# LTC2983_Group.net
KiCad netlist of a schematic drawn in Altium Designer
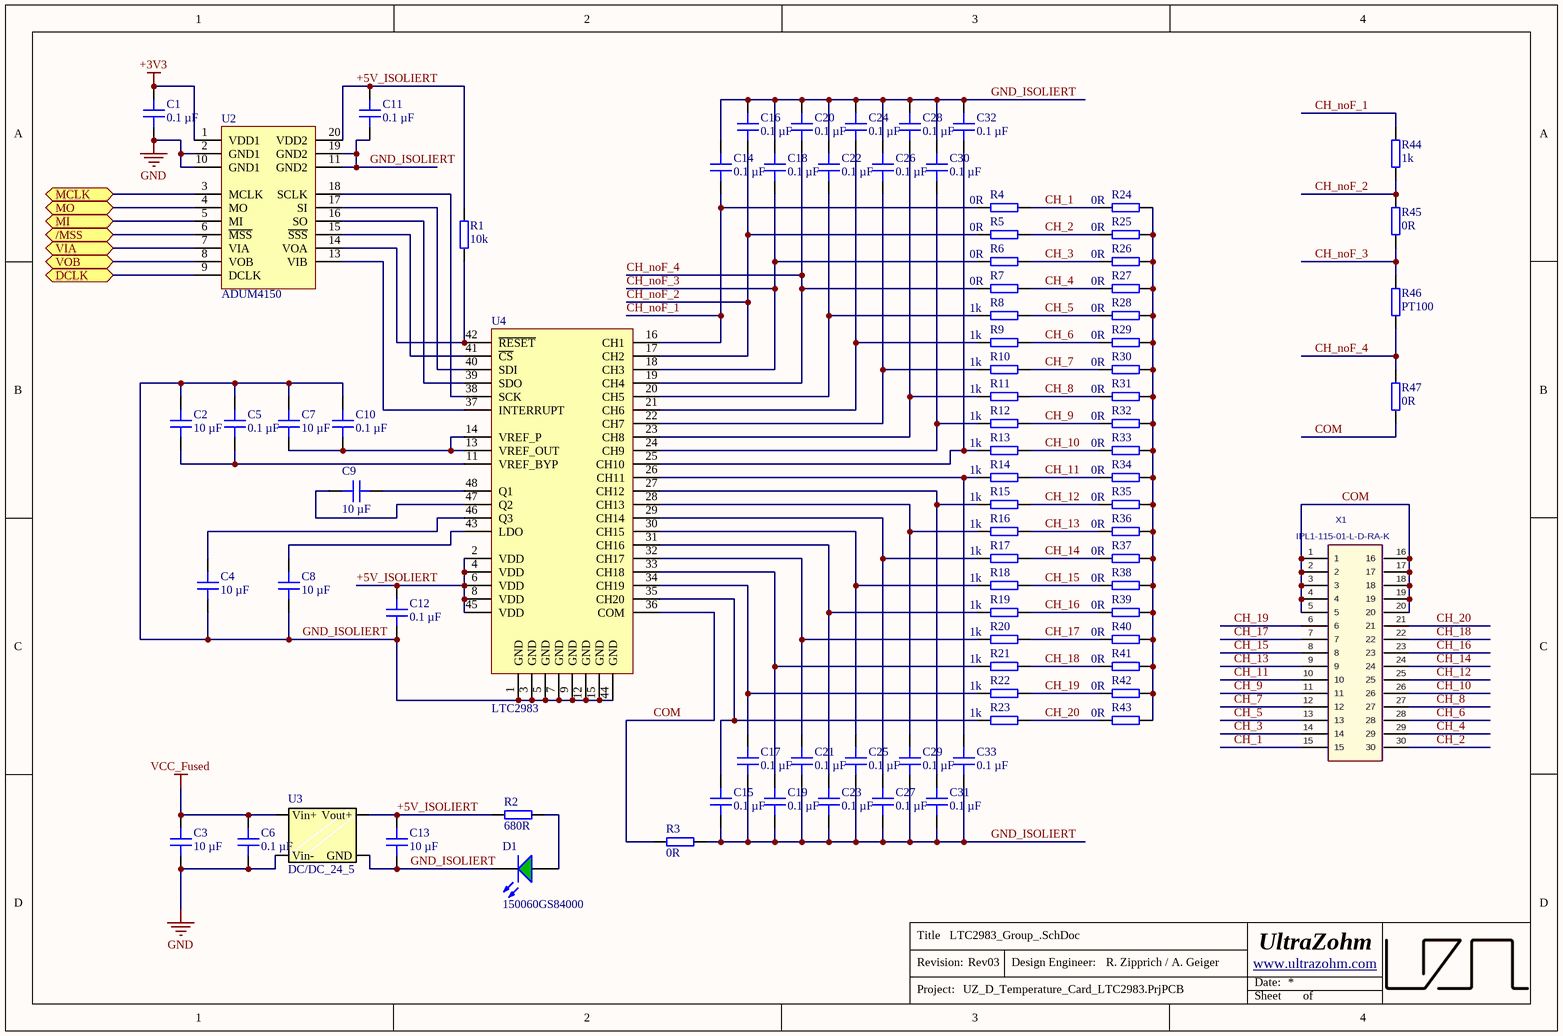
[diagram p0: LTC2983_Group_.SchDoc]

(export (version "E")
  (design (tool "Eeschema 10.0.6"))
  (components
    (comp (ref "C1")
      (value "0.1 µF")
      (footprint "C_0603")
      (description "Capacitor 0603, 50 VDC, 0.1 µF, X7R")
      (fields
        (field (name "MANUFACTURER PART NUMBER") "C0603X104K5RAC7411")
        (field (name "MANUFACTURER") "KEMET")
        (field (name "CREATED FROM") "MGremer")
      )
      (libsource (lib "user") (part "Capacitor"))
    )
    (comp (ref "C2")
      (value "10 µF")
      (footprint "C_0603")
      (description "Capacitor 0603, 6.3 VDC, 10 µF, X5R")
      (fields
        (field (name "MANUFACTURER PART NUMBER") "GRM185R60J106ME15D")
        (field (name "MANUFACTURER") "muRata")
        (field (name "CREATED FROM") "MGremer")
      )
      (libsource (lib "user") (part "Capacitor"))
    )
    (comp (ref "C3")
      (value "10 µF")
      (footprint "C_0603")
      (description "Capacitor 0603, 6.3 VDC, 10 µF, X5R")
      (fields
        (field (name "MANUFACTURER PART NUMBER") "GRM185R60J106ME15D")
        (field (name "MANUFACTURER") "muRata")
        (field (name "CREATED FROM") "MGremer")
      )
      (libsource (lib "user") (part "Capacitor"))
    )
    (comp (ref "C4")
      (value "10 µF")
      (footprint "C_0603")
      (description "Capacitor 0603, 6.3 VDC, 10 µF, X5R")
      (fields
        (field (name "MANUFACTURER PART NUMBER") "GRM185R60J106ME15D")
        (field (name "MANUFACTURER") "muRata")
        (field (name "CREATED FROM") "MGremer")
      )
      (libsource (lib "user") (part "Capacitor"))
    )
    (comp (ref "C5")
      (value "0.1 µF")
      (footprint "C_0603")
      (description "Capacitor 0603, 50 VDC, 0.1 µF, X7R")
      (fields
        (field (name "MANUFACTURER PART NUMBER") "C0603X104K5RAC7411")
        (field (name "MANUFACTURER") "KEMET")
        (field (name "CREATED FROM") "MGremer")
      )
      (libsource (lib "user") (part "Capacitor"))
    )
    (comp (ref "C6")
      (value "0.1 µF")
      (footprint "C_0603")
      (description "Capacitor 0603, 50 VDC, 0.1 µF, X7R")
      (fields
        (field (name "MANUFACTURER PART NUMBER") "C0603X104K5RAC7411")
        (field (name "MANUFACTURER") "KEMET")
        (field (name "CREATED FROM") "MGremer")
      )
      (libsource (lib "user") (part "Capacitor"))
    )
    (comp (ref "C7")
      (value "10 µF")
      (footprint "C_0603")
      (description "Capacitor 0603, 6.3 VDC, 10 µF, X5R")
      (fields
        (field (name "MANUFACTURER PART NUMBER") "GRM185R60J106ME15D")
        (field (name "MANUFACTURER") "muRata")
        (field (name "CREATED FROM") "MGremer")
      )
      (libsource (lib "user") (part "Capacitor"))
    )
    (comp (ref "C8")
      (value "10 µF")
      (footprint "C_0603")
      (description "Capacitor 0603, 6.3 VDC, 10 µF, X5R")
      (fields
        (field (name "MANUFACTURER PART NUMBER") "GRM185R60J106ME15D")
        (field (name "MANUFACTURER") "muRata")
        (field (name "CREATED FROM") "MGremer")
      )
      (libsource (lib "user") (part "Capacitor"))
    )
    (comp (ref "C9")
      (value "10 µF")
      (footprint "C_0603")
      (description "Capacitor 0603, 6.3 VDC, 10 µF, X5R")
      (fields
        (field (name "MANUFACTURER PART NUMBER") "GRM185R60J106ME15D")
        (field (name "MANUFACTURER") "muRata")
        (field (name "CREATED FROM") "MGremer")
      )
      (libsource (lib "user") (part "Capacitor"))
    )
    (comp (ref "C10")
      (value "0.1 µF")
      (footprint "C_0603")
      (description "Capacitor 0603, 50 VDC, 0.1 µF, X7R")
      (fields
        (field (name "MANUFACTURER PART NUMBER") "C0603X104K5RAC7411")
        (field (name "MANUFACTURER") "KEMET")
        (field (name "CREATED FROM") "MGremer")
      )
      (libsource (lib "user") (part "Capacitor"))
    )
    (comp (ref "C11")
      (value "0.1 µF")
      (footprint "C_0603")
      (description "Capacitor 0603, 50 VDC, 0.1 µF, X7R")
      (fields
        (field (name "MANUFACTURER PART NUMBER") "C0603X104K5RAC7411")
        (field (name "MANUFACTURER") "KEMET")
        (field (name "CREATED FROM") "MGremer")
      )
      (libsource (lib "user") (part "Capacitor"))
    )
    (comp (ref "C12")
      (value "0.1 µF")
      (footprint "C_0603")
      (description "Capacitor 0603, 50 VDC, 0.1 µF, X7R")
      (fields
        (field (name "MANUFACTURER PART NUMBER") "C0603X104K5RAC7411")
        (field (name "MANUFACTURER") "KEMET")
        (field (name "CREATED FROM") "MGremer")
      )
      (libsource (lib "user") (part "Capacitor"))
    )
    (comp (ref "C13")
      (value "10 µF")
      (footprint "C_0603")
      (description "Capacitor 0603, 6.3 VDC, 10 µF, X5R")
      (fields
        (field (name "MANUFACTURER PART NUMBER") "GRM185R60J106ME15D")
        (field (name "MANUFACTURER") "muRata")
        (field (name "CREATED FROM") "MGremer")
      )
      (libsource (lib "user") (part "Capacitor"))
    )
    (comp (ref "C14")
      (value "0.1 µF")
      (footprint "C_0603")
      (description "Capacitor 0603, 50 VDC, 0.1 µF, X7R")
      (fields
        (field (name "MANUFACTURER PART NUMBER") "C0603X104K5RAC7411")
        (field (name "MANUFACTURER") "KEMET")
        (field (name "CREATED FROM") "MGremer")
      )
      (libsource (lib "user") (part "Capacitor"))
    )
    (comp (ref "C15")
      (value "0.1 µF")
      (footprint "C_0603")
      (description "Capacitor 0603, 50 VDC, 0.1 µF, X7R")
      (fields
        (field (name "MANUFACTURER PART NUMBER") "C0603X104K5RAC7411")
        (field (name "MANUFACTURER") "KEMET")
        (field (name "CREATED FROM") "MGremer")
      )
      (libsource (lib "user") (part "Capacitor"))
    )
    (comp (ref "C16")
      (value "0.1 µF")
      (footprint "C_0603")
      (description "Capacitor 0603, 50 VDC, 0.1 µF, X7R")
      (fields
        (field (name "MANUFACTURER PART NUMBER") "C0603X104K5RAC7411")
        (field (name "MANUFACTURER") "KEMET")
        (field (name "CREATED FROM") "MGremer")
      )
      (libsource (lib "user") (part "Capacitor"))
    )
    (comp (ref "C17")
      (value "0.1 µF")
      (footprint "C_0603")
      (description "Capacitor 0603, 50 VDC, 0.1 µF, X7R")
      (fields
        (field (name "MANUFACTURER PART NUMBER") "C0603X104K5RAC7411")
        (field (name "MANUFACTURER") "KEMET")
        (field (name "CREATED FROM") "MGremer")
      )
      (libsource (lib "user") (part "Capacitor"))
    )
    (comp (ref "C18")
      (value "0.1 µF")
      (footprint "C_0603")
      (description "Capacitor 0603, 50 VDC, 0.1 µF, X7R")
      (fields
        (field (name "MANUFACTURER PART NUMBER") "C0603X104K5RAC7411")
        (field (name "MANUFACTURER") "KEMET")
        (field (name "CREATED FROM") "MGremer")
      )
      (libsource (lib "user") (part "Capacitor"))
    )
    (comp (ref "C19")
      (value "0.1 µF")
      (footprint "C_0603")
      (description "Capacitor 0603, 50 VDC, 0.1 µF, X7R")
      (fields
        (field (name "MANUFACTURER PART NUMBER") "C0603X104K5RAC7411")
        (field (name "MANUFACTURER") "KEMET")
        (field (name "CREATED FROM") "MGremer")
      )
      (libsource (lib "user") (part "Capacitor"))
    )
    (comp (ref "C20")
      (value "0.1 µF")
      (footprint "C_0603")
      (description "Capacitor 0603, 50 VDC, 0.1 µF, X7R")
      (fields
        (field (name "MANUFACTURER PART NUMBER") "C0603X104K5RAC7411")
        (field (name "MANUFACTURER") "KEMET")
        (field (name "CREATED FROM") "MGremer")
      )
      (libsource (lib "user") (part "Capacitor"))
    )
    (comp (ref "C21")
      (value "0.1 µF")
      (footprint "C_0603")
      (description "Capacitor 0603, 50 VDC, 0.1 µF, X7R")
      (fields
        (field (name "MANUFACTURER PART NUMBER") "C0603X104K5RAC7411")
        (field (name "MANUFACTURER") "KEMET")
        (field (name "CREATED FROM") "MGremer")
      )
      (libsource (lib "user") (part "Capacitor"))
    )
    (comp (ref "C22")
      (value "0.1 µF")
      (footprint "C_0603")
      (description "Capacitor 0603, 50 VDC, 0.1 µF, X7R")
      (fields
        (field (name "MANUFACTURER PART NUMBER") "C0603X104K5RAC7411")
        (field (name "MANUFACTURER") "KEMET")
        (field (name "CREATED FROM") "MGremer")
      )
      (libsource (lib "user") (part "Capacitor"))
    )
    (comp (ref "C23")
      (value "0.1 µF")
      (footprint "C_0603")
      (description "Capacitor 0603, 50 VDC, 0.1 µF, X7R")
      (fields
        (field (name "MANUFACTURER PART NUMBER") "C0603X104K5RAC7411")
        (field (name "MANUFACTURER") "KEMET")
        (field (name "CREATED FROM") "MGremer")
      )
      (libsource (lib "user") (part "Capacitor"))
    )
    (comp (ref "C24")
      (value "0.1 µF")
      (footprint "C_0603")
      (description "Capacitor 0603, 50 VDC, 0.1 µF, X7R")
      (fields
        (field (name "MANUFACTURER PART NUMBER") "C0603X104K5RAC7411")
        (field (name "MANUFACTURER") "KEMET")
        (field (name "CREATED FROM") "MGremer")
      )
      (libsource (lib "user") (part "Capacitor"))
    )
    (comp (ref "C25")
      (value "0.1 µF")
      (footprint "C_0603")
      (description "Capacitor 0603, 50 VDC, 0.1 µF, X7R")
      (fields
        (field (name "MANUFACTURER PART NUMBER") "C0603X104K5RAC7411")
        (field (name "MANUFACTURER") "KEMET")
        (field (name "CREATED FROM") "MGremer")
      )
      (libsource (lib "user") (part "Capacitor"))
    )
    (comp (ref "C26")
      (value "0.1 µF")
      (footprint "C_0603")
      (description "Capacitor 0603, 50 VDC, 0.1 µF, X7R")
      (fields
        (field (name "MANUFACTURER PART NUMBER") "C0603X104K5RAC7411")
        (field (name "MANUFACTURER") "KEMET")
        (field (name "CREATED FROM") "MGremer")
      )
      (libsource (lib "user") (part "Capacitor"))
    )
    (comp (ref "C27")
      (value "0.1 µF")
      (footprint "C_0603")
      (description "Capacitor 0603, 50 VDC, 0.1 µF, X7R")
      (fields
        (field (name "MANUFACTURER PART NUMBER") "C0603X104K5RAC7411")
        (field (name "MANUFACTURER") "KEMET")
        (field (name "CREATED FROM") "MGremer")
      )
      (libsource (lib "user") (part "Capacitor"))
    )
    (comp (ref "C28")
      (value "0.1 µF")
      (footprint "C_0603")
      (description "Capacitor 0603, 50 VDC, 0.1 µF, X7R")
      (fields
        (field (name "MANUFACTURER PART NUMBER") "C0603X104K5RAC7411")
        (field (name "MANUFACTURER") "KEMET")
        (field (name "CREATED FROM") "MGremer")
      )
      (libsource (lib "user") (part "Capacitor"))
    )
    (comp (ref "C29")
      (value "0.1 µF")
      (footprint "C_0603")
      (description "Capacitor 0603, 50 VDC, 0.1 µF, X7R")
      (fields
        (field (name "MANUFACTURER PART NUMBER") "C0603X104K5RAC7411")
        (field (name "MANUFACTURER") "KEMET")
        (field (name "CREATED FROM") "MGremer")
      )
      (libsource (lib "user") (part "Capacitor"))
    )
    (comp (ref "C30")
      (value "0.1 µF")
      (footprint "C_0603")
      (description "Capacitor 0603, 50 VDC, 0.1 µF, X7R")
      (fields
        (field (name "MANUFACTURER PART NUMBER") "C0603X104K5RAC7411")
        (field (name "MANUFACTURER") "KEMET")
        (field (name "CREATED FROM") "MGremer")
      )
      (libsource (lib "user") (part "Capacitor"))
    )
    (comp (ref "C31")
      (value "0.1 µF")
      (footprint "C_0603")
      (description "Capacitor 0603, 50 VDC, 0.1 µF, X7R")
      (fields
        (field (name "MANUFACTURER PART NUMBER") "C0603X104K5RAC7411")
        (field (name "MANUFACTURER") "KEMET")
        (field (name "CREATED FROM") "MGremer")
      )
      (libsource (lib "user") (part "Capacitor"))
    )
    (comp (ref "C32")
      (value "0.1 µF")
      (footprint "C_0603")
      (description "Capacitor 0603, 50 VDC, 0.1 µF, X7R")
      (fields
        (field (name "MANUFACTURER PART NUMBER") "C0603X104K5RAC7411")
        (field (name "MANUFACTURER") "KEMET")
        (field (name "CREATED FROM") "MGremer")
      )
      (libsource (lib "user") (part "Capacitor"))
    )
    (comp (ref "C33")
      (value "0.1 µF")
      (footprint "C_0603")
      (description "Capacitor 0603, 50 VDC, 0.1 µF, X7R")
      (fields
        (field (name "MANUFACTURER PART NUMBER") "C0603X104K5RAC7411")
        (field (name "MANUFACTURER") "KEMET")
        (field (name "CREATED FROM") "MGremer")
      )
      (libsource (lib "user") (part "Capacitor"))
    )
    (comp (ref "D1")
      (value "150060GS84000")
      (footprint "WL-SMCW_0603")
      (description "WL-SMCW SMD Mono-color Chip LED Waterclear Green")
      (fields
        (field (name "MANUFACTURER") "Wuerth Elektronik")
        (field (name "LCSC PART NUMBER") "C72043")
        (field (name "CREATED FROM") "MGremer")
      )
      (libsource (lib "user") (part "LED_Green"))
    )
    (comp (ref "R1")
      (value "10k")
      (footprint "RES 0603_1608")
      (description "SMD resistor E24 series")
      (fields
        (field (name "MANUFACTURER PART NUMBER") "RK73B1JTTD103J")
        (field (name "MANUFACTURER") "KOA Speer")
        (field (name "CREATED FROM") "MGremer")
      )
      (libsource (lib "user") (part "Resistor"))
    )
    (comp (ref "R2")
      (value "680R")
      (footprint "RES 0603_1608")
      (description "SMD resistor E24 series")
      (fields
        (field (name "MANUFACTURER PART NUMBER") "RK73B1JTTDD681J")
        (field (name "MANUFACTURER") "KOA Speer")
        (field (name "CREATED FROM") "MGremer")
      )
      (libsource (lib "user") (part "Resistor"))
    )
    (comp (ref "R3")
      (value "0R")
      (footprint "RES 0603_1608")
      (description "SMD resistor E24 series")
      (fields
        (field (name "MANUFACTURER PART NUMBER") "RC0603JR-070RL")
        (field (name "MANUFACTURER") "YAGEO")
        (field (name "CREATED FROM") "MGremer")
      )
      (libsource (lib "user") (part "Resistor"))
    )
    (comp (ref "R4")
      (value "0R")
      (footprint "RES 0603_1608")
      (description "SMD resistor E24 series")
      (fields
        (field (name "MANUFACTURER PART NUMBER") "RC0603JR-070RL")
        (field (name "MANUFACTURER") "YAGEO")
        (field (name "CREATED FROM") "MGremer")
      )
      (libsource (lib "user") (part "Resistor"))
    )
    (comp (ref "R5")
      (value "0R")
      (footprint "RES 0603_1608")
      (description "SMD resistor E24 series")
      (fields
        (field (name "MANUFACTURER PART NUMBER") "RC0603JR-070RL")
        (field (name "MANUFACTURER") "YAGEO")
        (field (name "CREATED FROM") "MGremer")
      )
      (libsource (lib "user") (part "Resistor"))
    )
    (comp (ref "R6")
      (value "0R")
      (footprint "RES 0603_1608")
      (description "SMD resistor E24 series")
      (fields
        (field (name "MANUFACTURER PART NUMBER") "RC0603JR-070RL")
        (field (name "MANUFACTURER") "YAGEO")
        (field (name "CREATED FROM") "MGremer")
      )
      (libsource (lib "user") (part "Resistor"))
    )
    (comp (ref "R7")
      (value "0R")
      (footprint "RES 0603_1608")
      (description "SMD resistor E24 series")
      (fields
        (field (name "MANUFACTURER PART NUMBER") "RC0603JR-070RL")
        (field (name "MANUFACTURER") "YAGEO")
        (field (name "CREATED FROM") "MGremer")
      )
      (libsource (lib "user") (part "Resistor"))
    )
    (comp (ref "R8")
      (value "1k")
      (footprint "RES 0603_1608")
      (description "SMD resistor E24 series")
      (fields
        (field (name "MANUFACTURER PART NUMBER") "0603WAF1001T5E")
        (field (name "MANUFACTURER") "UNI-ROYAL")
        (field (name "CREATED FROM") "AGeiger")
      )
      (libsource (lib "user") (part "Resistor"))
    )
    (comp (ref "R9")
      (value "1k")
      (footprint "RES 0603_1608")
      (description "SMD resistor E24 series")
      (fields
        (field (name "MANUFACTURER PART NUMBER") "0603WAF1001T5E")
        (field (name "MANUFACTURER") "UNI-ROYAL")
        (field (name "CREATED FROM") "AGeiger")
      )
      (libsource (lib "user") (part "Resistor"))
    )
    (comp (ref "R10")
      (value "1k")
      (footprint "RES 0603_1608")
      (description "SMD resistor E24 series")
      (fields
        (field (name "MANUFACTURER PART NUMBER") "0603WAF1001T5E")
        (field (name "MANUFACTURER") "UNI-ROYAL")
        (field (name "CREATED FROM") "AGeiger")
      )
      (libsource (lib "user") (part "Resistor"))
    )
    (comp (ref "R11")
      (value "1k")
      (footprint "RES 0603_1608")
      (description "SMD resistor E24 series")
      (fields
        (field (name "MANUFACTURER PART NUMBER") "0603WAF1001T5E")
        (field (name "MANUFACTURER") "UNI-ROYAL")
        (field (name "CREATED FROM") "AGeiger")
      )
      (libsource (lib "user") (part "Resistor"))
    )
    (comp (ref "R12")
      (value "1k")
      (footprint "RES 0603_1608")
      (description "SMD resistor E24 series")
      (fields
        (field (name "MANUFACTURER PART NUMBER") "0603WAF1001T5E")
        (field (name "MANUFACTURER") "UNI-ROYAL")
        (field (name "CREATED FROM") "AGeiger")
      )
      (libsource (lib "user") (part "Resistor"))
    )
    (comp (ref "R13")
      (value "1k")
      (footprint "RES 0603_1608")
      (description "SMD resistor E24 series")
      (fields
        (field (name "MANUFACTURER PART NUMBER") "0603WAF1001T5E")
        (field (name "MANUFACTURER") "UNI-ROYAL")
        (field (name "CREATED FROM") "AGeiger")
      )
      (libsource (lib "user") (part "Resistor"))
    )
    (comp (ref "R14")
      (value "1k")
      (footprint "RES 0603_1608")
      (description "SMD resistor E24 series")
      (fields
        (field (name "MANUFACTURER PART NUMBER") "0603WAF1001T5E")
        (field (name "MANUFACTURER") "UNI-ROYAL")
        (field (name "CREATED FROM") "AGeiger")
      )
      (libsource (lib "user") (part "Resistor"))
    )
    (comp (ref "R15")
      (value "1k")
      (footprint "RES 0603_1608")
      (description "SMD resistor E24 series")
      (fields
        (field (name "MANUFACTURER PART NUMBER") "0603WAF1001T5E")
        (field (name "MANUFACTURER") "UNI-ROYAL")
        (field (name "CREATED FROM") "AGeiger")
      )
      (libsource (lib "user") (part "Resistor"))
    )
    (comp (ref "R16")
      (value "1k")
      (footprint "RES 0603_1608")
      (description "SMD resistor E24 series")
      (fields
        (field (name "MANUFACTURER PART NUMBER") "0603WAF1001T5E")
        (field (name "MANUFACTURER") "UNI-ROYAL")
        (field (name "CREATED FROM") "AGeiger")
      )
      (libsource (lib "user") (part "Resistor"))
    )
    (comp (ref "R17")
      (value "1k")
      (footprint "RES 0603_1608")
      (description "SMD resistor E24 series")
      (fields
        (field (name "MANUFACTURER PART NUMBER") "0603WAF1001T5E")
        (field (name "MANUFACTURER") "UNI-ROYAL")
        (field (name "CREATED FROM") "AGeiger")
      )
      (libsource (lib "user") (part "Resistor"))
    )
    (comp (ref "R18")
      (value "1k")
      (footprint "RES 0603_1608")
      (description "SMD resistor E24 series")
      (fields
        (field (name "MANUFACTURER PART NUMBER") "0603WAF1001T5E")
        (field (name "MANUFACTURER") "UNI-ROYAL")
        (field (name "CREATED FROM") "AGeiger")
      )
      (libsource (lib "user") (part "Resistor"))
    )
    (comp (ref "R19")
      (value "1k")
      (footprint "RES 0603_1608")
      (description "SMD resistor E24 series")
      (fields
        (field (name "MANUFACTURER PART NUMBER") "0603WAF1001T5E")
        (field (name "MANUFACTURER") "UNI-ROYAL")
        (field (name "CREATED FROM") "AGeiger")
      )
      (libsource (lib "user") (part "Resistor"))
    )
    (comp (ref "R20")
      (value "1k")
      (footprint "RES 0603_1608")
      (description "SMD resistor E24 series")
      (fields
        (field (name "MANUFACTURER PART NUMBER") "0603WAF1001T5E")
        (field (name "MANUFACTURER") "UNI-ROYAL")
        (field (name "CREATED FROM") "AGeiger")
      )
      (libsource (lib "user") (part "Resistor"))
    )
    (comp (ref "R21")
      (value "1k")
      (footprint "RES 0603_1608")
      (description "SMD resistor E24 series")
      (fields
        (field (name "MANUFACTURER PART NUMBER") "0603WAF1001T5E")
        (field (name "MANUFACTURER") "UNI-ROYAL")
        (field (name "CREATED FROM") "AGeiger")
      )
      (libsource (lib "user") (part "Resistor"))
    )
    (comp (ref "R22")
      (value "1k")
      (footprint "RES 0603_1608")
      (description "SMD resistor E24 series")
      (fields
        (field (name "MANUFACTURER PART NUMBER") "0603WAF1001T5E")
        (field (name "MANUFACTURER") "UNI-ROYAL")
        (field (name "CREATED FROM") "AGeiger")
      )
      (libsource (lib "user") (part "Resistor"))
    )
    (comp (ref "R23")
      (value "1k")
      (footprint "RES 0603_1608")
      (description "SMD resistor E24 series")
      (fields
        (field (name "MANUFACTURER PART NUMBER") "0603WAF1001T5E")
        (field (name "MANUFACTURER") "UNI-ROYAL")
        (field (name "CREATED FROM") "AGeiger")
      )
      (libsource (lib "user") (part "Resistor"))
    )
    (comp (ref "R24")
      (value "0R")
      (footprint "RES 0603_1608")
      (description "SMD resistor E24 series")
      (fields
        (field (name "MANUFACTURER PART NUMBER") "RC0603JR-070RL")
        (field (name "MANUFACTURER") "YAGEO")
        (field (name "CREATED FROM") "MGremer")
      )
      (libsource (lib "user") (part "Resistor"))
    )
    (comp (ref "R25")
      (value "0R")
      (footprint "RES 0603_1608")
      (description "SMD resistor E24 series")
      (fields
        (field (name "MANUFACTURER PART NUMBER") "RC0603JR-070RL")
        (field (name "MANUFACTURER") "YAGEO")
        (field (name "CREATED FROM") "MGremer")
      )
      (libsource (lib "user") (part "Resistor"))
    )
    (comp (ref "R26")
      (value "0R")
      (footprint "RES 0603_1608")
      (description "SMD resistor E24 series")
      (fields
        (field (name "MANUFACTURER PART NUMBER") "RC0603JR-070RL")
        (field (name "MANUFACTURER") "YAGEO")
        (field (name "CREATED FROM") "MGremer")
      )
      (libsource (lib "user") (part "Resistor"))
    )
    (comp (ref "R27")
      (value "0R")
      (footprint "RES 0603_1608")
      (description "SMD resistor E24 series")
      (fields
        (field (name "MANUFACTURER PART NUMBER") "RC0603JR-070RL")
        (field (name "MANUFACTURER") "YAGEO")
        (field (name "CREATED FROM") "MGremer")
      )
      (libsource (lib "user") (part "Resistor"))
    )
    (comp (ref "R28")
      (value "0R")
      (footprint "RES 0603_1608")
      (description "SMD resistor E24 series")
      (fields
        (field (name "MANUFACTURER PART NUMBER") "RC0603JR-070RL")
        (field (name "MANUFACTURER") "YAGEO")
        (field (name "CREATED FROM") "MGremer")
      )
      (libsource (lib "user") (part "Resistor"))
    )
    (comp (ref "R29")
      (value "0R")
      (footprint "RES 0603_1608")
      (description "SMD resistor E24 series")
      (fields
        (field (name "MANUFACTURER PART NUMBER") "RC0603JR-070RL")
        (field (name "MANUFACTURER") "YAGEO")
        (field (name "CREATED FROM") "MGremer")
      )
      (libsource (lib "user") (part "Resistor"))
    )
    (comp (ref "R30")
      (value "0R")
      (footprint "RES 0603_1608")
      (description "SMD resistor E24 series")
      (fields
        (field (name "MANUFACTURER PART NUMBER") "RC0603JR-070RL")
        (field (name "MANUFACTURER") "YAGEO")
        (field (name "CREATED FROM") "MGremer")
      )
      (libsource (lib "user") (part "Resistor"))
    )
    (comp (ref "R31")
      (value "0R")
      (footprint "RES 0603_1608")
      (description "SMD resistor E24 series")
      (fields
        (field (name "MANUFACTURER PART NUMBER") "RC0603JR-070RL")
        (field (name "MANUFACTURER") "YAGEO")
        (field (name "CREATED FROM") "MGremer")
      )
      (libsource (lib "user") (part "Resistor"))
    )
    (comp (ref "R32")
      (value "0R")
      (footprint "RES 0603_1608")
      (description "SMD resistor E24 series")
      (fields
        (field (name "MANUFACTURER PART NUMBER") "RC0603JR-070RL")
        (field (name "MANUFACTURER") "YAGEO")
        (field (name "CREATED FROM") "MGremer")
      )
      (libsource (lib "user") (part "Resistor"))
    )
    (comp (ref "R33")
      (value "0R")
      (footprint "RES 0603_1608")
      (description "SMD resistor E24 series")
      (fields
        (field (name "MANUFACTURER PART NUMBER") "RC0603JR-070RL")
        (field (name "MANUFACTURER") "YAGEO")
        (field (name "CREATED FROM") "MGremer")
      )
      (libsource (lib "user") (part "Resistor"))
    )
    (comp (ref "R34")
      (value "0R")
      (footprint "RES 0603_1608")
      (description "SMD resistor E24 series")
      (fields
        (field (name "MANUFACTURER PART NUMBER") "RC0603JR-070RL")
        (field (name "MANUFACTURER") "YAGEO")
        (field (name "CREATED FROM") "MGremer")
      )
      (libsource (lib "user") (part "Resistor"))
    )
    (comp (ref "R35")
      (value "0R")
      (footprint "RES 0603_1608")
      (description "SMD resistor E24 series")
      (fields
        (field (name "MANUFACTURER PART NUMBER") "RC0603JR-070RL")
        (field (name "MANUFACTURER") "YAGEO")
        (field (name "CREATED FROM") "MGremer")
      )
      (libsource (lib "user") (part "Resistor"))
    )
    (comp (ref "R36")
      (value "0R")
      (footprint "RES 0603_1608")
      (description "SMD resistor E24 series")
      (fields
        (field (name "MANUFACTURER PART NUMBER") "RC0603JR-070RL")
        (field (name "MANUFACTURER") "YAGEO")
        (field (name "CREATED FROM") "MGremer")
      )
      (libsource (lib "user") (part "Resistor"))
    )
    (comp (ref "R37")
      (value "0R")
      (footprint "RES 0603_1608")
      (description "SMD resistor E24 series")
      (fields
        (field (name "MANUFACTURER PART NUMBER") "RC0603JR-070RL")
        (field (name "MANUFACTURER") "YAGEO")
        (field (name "CREATED FROM") "MGremer")
      )
      (libsource (lib "user") (part "Resistor"))
    )
    (comp (ref "R38")
      (value "0R")
      (footprint "RES 0603_1608")
      (description "SMD resistor E24 series")
      (fields
        (field (name "MANUFACTURER PART NUMBER") "RC0603JR-070RL")
        (field (name "MANUFACTURER") "YAGEO")
        (field (name "CREATED FROM") "MGremer")
      )
      (libsource (lib "user") (part "Resistor"))
    )
    (comp (ref "R39")
      (value "0R")
      (footprint "RES 0603_1608")
      (description "SMD resistor E24 series")
      (fields
        (field (name "MANUFACTURER PART NUMBER") "RC0603JR-070RL")
        (field (name "MANUFACTURER") "YAGEO")
        (field (name "CREATED FROM") "MGremer")
      )
      (libsource (lib "user") (part "Resistor"))
    )
    (comp (ref "R40")
      (value "0R")
      (footprint "RES 0603_1608")
      (description "SMD resistor E24 series")
      (fields
        (field (name "MANUFACTURER PART NUMBER") "RC0603JR-070RL")
        (field (name "MANUFACTURER") "YAGEO")
        (field (name "CREATED FROM") "MGremer")
      )
      (libsource (lib "user") (part "Resistor"))
    )
    (comp (ref "R41")
      (value "0R")
      (footprint "RES 0603_1608")
      (description "SMD resistor E24 series")
      (fields
        (field (name "MANUFACTURER PART NUMBER") "RC0603JR-070RL")
        (field (name "MANUFACTURER") "YAGEO")
        (field (name "CREATED FROM") "MGremer")
      )
      (libsource (lib "user") (part "Resistor"))
    )
    (comp (ref "R42")
      (value "0R")
      (footprint "RES 0603_1608")
      (description "SMD resistor E24 series")
      (fields
        (field (name "MANUFACTURER PART NUMBER") "RC0603JR-070RL")
        (field (name "MANUFACTURER") "YAGEO")
        (field (name "CREATED FROM") "MGremer")
      )
      (libsource (lib "user") (part "Resistor"))
    )
    (comp (ref "R43")
      (value "0R")
      (footprint "RES 0603_1608")
      (description "SMD resistor E24 series")
      (fields
        (field (name "MANUFACTURER PART NUMBER") "RC0603JR-070RL")
        (field (name "MANUFACTURER") "YAGEO")
        (field (name "CREATED FROM") "MGremer")
      )
      (libsource (lib "user") (part "Resistor"))
    )
    (comp (ref "R44")
      (value "1k")
      (footprint "RES 0603_1608")
      (description "SMD resistor 0.1%")
      (fields
        (field (name "MANUFACTURER PART NUMBER") "PCF-W0603LF-03-1001-B-P-LT")
        (field (name "MANUFACTURER") "IRC / TT Electronics")
        (field (name "CREATED FROM") "MGremer")
      )
      (libsource (lib "user") (part "Resistor"))
    )
    (comp (ref "R45")
      (value "0R")
      (footprint "RES 0603_1608")
      (description "SMD resistor E24 series")
      (fields
        (field (name "MANUFACTURER PART NUMBER") "RC0603JR-070RL")
        (field (name "MANUFACTURER") "YAGEO")
        (field (name "CREATED FROM") "MGremer")
      )
      (libsource (lib "user") (part "Resistor"))
    )
    (comp (ref "R46")
      (value "PT100")
      (footprint "RES 0603_1608")
      (description "SMD resistor 0.1%")
      (fields
        (field (name "MANUFACTURER PART NUMBER") "PCF-W0603LF-03-1001-B-P-LT")
        (field (name "MANUFACTURER") "IRC / TT Electronics")
        (field (name "CREATED FROM") "MGremer")
      )
      (libsource (lib "user") (part "Resistor"))
    )
    (comp (ref "R47")
      (value "0R")
      (footprint "RES 0603_1608")
      (description "SMD resistor E24 series")
      (fields
        (field (name "MANUFACTURER PART NUMBER") "RC0603JR-070RL")
        (field (name "MANUFACTURER") "YAGEO")
        (field (name "CREATED FROM") "MGremer")
      )
      (libsource (lib "user") (part "Resistor"))
    )
    (comp (ref "U2")
      (value "ADUM4150")
      (footprint "SOIC-20-ADUM4150")
      (fields (field (name "LCSC PART NUMBER") "C660948"))
      (libsource (lib "PRJ_LIB_LTC2983_Card") (part "ADUM4150"))
    )
    (comp (ref "U3")
      (value "DC/DC_24_5")
      (footprint "SIP4DCDC")
      (fields (field (name "LCSC PART NUMBER") "C970824"))
      (libsource (lib "PRJ_LIB_LTC2983_Card") (part "DC/DC_Single"))
    )
    (comp (ref "U4")
      (value "LTC2983")
      (footprint "48_LGFP(7x7)")
      (fields (field (name "LCSC PART NUMBER") "C427448"))
      (libsource (lib "PRJ_LIB_LTC2983_Card") (part "LTC2983"))
    )
    (comp (ref "X1")
      (value "IPL1-115-01-L-D-RA-K")
      (footprint "IPL1-115-01-XX-D-RA")
      (description "Terminal Assembly, Double Row, Right Angle, Thru-Hole, 2.54 mm x 2.54 mm Pitch, 30 Pins")
      (fields
        (field (name "MANUFACTURER") "SAMTEC")
        (field (name "LCSC PART NUMBER") "C7423882")
        (field (name "CREATED FROM") "TWendt")
      )
      (libsource (lib "user") (part "IPL1-115-01-XX-D-XX"))
    )
  )
  (nets
    (net (code "1") (name "+3V3") (class "Default")
      (node (ref "C1") (pin "2") (pinfunction "2_2") (pintype "passive"))
      (node (ref "U2") (pin "1") (pinfunction "VDD1_1") (pintype "passive"))
    )
    (net (code "2") (name "/+5V_ISOLIERT") (class "Default")
      (node (ref "C11") (pin "2") (pinfunction "2_2") (pintype "passive"))
      (node (ref "C12") (pin "2") (pinfunction "2_2") (pintype "passive"))
      (node (ref "C13") (pin "2") (pinfunction "2_2") (pintype "passive"))
      (node (ref "R1") (pin "2") (pinfunction "2_2") (pintype "passive"))
      (node (ref "R2") (pin "1") (pinfunction "1_1") (pintype "passive"))
      (node (ref "U2") (pin "20") (pinfunction "VDD2_20") (pintype "passive"))
      (node (ref "U3") (pin "6") (pinfunction "Vout+_6") (pintype "passive"))
      (node (ref "U4") (pin "2") (pinfunction "VDD_2") (pintype "passive"))
      (node (ref "U4") (pin "4") (pinfunction "VDD_4") (pintype "passive"))
      (node (ref "U4") (pin "45") (pinfunction "VDD_45") (pintype "passive"))
      (node (ref "U4") (pin "6") (pinfunction "VDD_6") (pintype "passive"))
      (node (ref "U4") (pin "8") (pinfunction "VDD_8") (pintype "passive"))
    )
    (net (code "3") (name "/CH_1") (class "Default")
      (node (ref "R24") (pin "1") (pinfunction "1_1") (pintype "passive"))
      (node (ref "R4") (pin "2") (pinfunction "2_2") (pintype "passive"))
      (node (ref "X1") (pin "15") (pinfunction "15_15") (pintype "passive"))
    )
    (net (code "4") (name "/CH_2") (class "Default")
      (node (ref "R25") (pin "1") (pinfunction "1_1") (pintype "passive"))
      (node (ref "R5") (pin "2") (pinfunction "2_2") (pintype "passive"))
      (node (ref "X1") (pin "30") (pinfunction "30_30") (pintype "passive"))
    )
    (net (code "5") (name "/CH_3") (class "Default")
      (node (ref "R26") (pin "1") (pinfunction "1_1") (pintype "passive"))
      (node (ref "R6") (pin "2") (pinfunction "2_2") (pintype "passive"))
      (node (ref "X1") (pin "14") (pinfunction "14_14") (pintype "passive"))
    )
    (net (code "6") (name "/CH_4") (class "Default")
      (node (ref "R27") (pin "1") (pinfunction "1_1") (pintype "passive"))
      (node (ref "R7") (pin "2") (pinfunction "2_2") (pintype "passive"))
      (node (ref "X1") (pin "29") (pinfunction "29_29") (pintype "passive"))
    )
    (net (code "7") (name "/CH_5") (class "Default")
      (node (ref "R28") (pin "1") (pinfunction "1_1") (pintype "passive"))
      (node (ref "R8") (pin "2") (pinfunction "2_2") (pintype "passive"))
      (node (ref "X1") (pin "13") (pinfunction "13_13") (pintype "passive"))
    )
    (net (code "8") (name "/CH_6") (class "Default")
      (node (ref "R29") (pin "1") (pinfunction "1_1") (pintype "passive"))
      (node (ref "R9") (pin "2") (pinfunction "2_2") (pintype "passive"))
      (node (ref "X1") (pin "28") (pinfunction "28_28") (pintype "passive"))
    )
    (net (code "9") (name "/CH_7") (class "Default")
      (node (ref "R10") (pin "2") (pinfunction "2_2") (pintype "passive"))
      (node (ref "R30") (pin "1") (pinfunction "1_1") (pintype "passive"))
      (node (ref "X1") (pin "12") (pinfunction "12_12") (pintype "passive"))
    )
    (net (code "10") (name "/CH_8") (class "Default")
      (node (ref "R11") (pin "2") (pinfunction "2_2") (pintype "passive"))
      (node (ref "R31") (pin "1") (pinfunction "1_1") (pintype "passive"))
      (node (ref "X1") (pin "27") (pinfunction "27_27") (pintype "passive"))
    )
    (net (code "11") (name "/CH_9") (class "Default")
      (node (ref "R12") (pin "2") (pinfunction "2_2") (pintype "passive"))
      (node (ref "R32") (pin "1") (pinfunction "1_1") (pintype "passive"))
      (node (ref "X1") (pin "11") (pinfunction "11_11") (pintype "passive"))
    )
    (net (code "12") (name "/CH_10") (class "Default")
      (node (ref "R13") (pin "2") (pinfunction "2_2") (pintype "passive"))
      (node (ref "R33") (pin "1") (pinfunction "1_1") (pintype "passive"))
      (node (ref "X1") (pin "26") (pinfunction "26_26") (pintype "passive"))
    )
    (net (code "13") (name "/CH_11") (class "Default")
      (node (ref "R14") (pin "2") (pinfunction "2_2") (pintype "passive"))
      (node (ref "R34") (pin "1") (pinfunction "1_1") (pintype "passive"))
      (node (ref "X1") (pin "10") (pinfunction "10_10") (pintype "passive"))
    )
    (net (code "14") (name "/CH_12") (class "Default")
      (node (ref "R15") (pin "2") (pinfunction "2_2") (pintype "passive"))
      (node (ref "R35") (pin "1") (pinfunction "1_1") (pintype "passive"))
      (node (ref "X1") (pin "25") (pinfunction "25_25") (pintype "passive"))
    )
    (net (code "15") (name "/CH_13") (class "Default")
      (node (ref "R16") (pin "2") (pinfunction "2_2") (pintype "passive"))
      (node (ref "R36") (pin "1") (pinfunction "1_1") (pintype "passive"))
      (node (ref "X1") (pin "9") (pinfunction "9_9") (pintype "passive"))
    )
    (net (code "16") (name "/CH_14") (class "Default")
      (node (ref "R17") (pin "2") (pinfunction "2_2") (pintype "passive"))
      (node (ref "R37") (pin "1") (pinfunction "1_1") (pintype "passive"))
      (node (ref "X1") (pin "24") (pinfunction "24_24") (pintype "passive"))
    )
    (net (code "17") (name "/CH_15") (class "Default")
      (node (ref "R18") (pin "2") (pinfunction "2_2") (pintype "passive"))
      (node (ref "R38") (pin "1") (pinfunction "1_1") (pintype "passive"))
      (node (ref "X1") (pin "8") (pinfunction "8_8") (pintype "passive"))
    )
    (net (code "18") (name "/CH_16") (class "Default")
      (node (ref "R19") (pin "2") (pinfunction "2_2") (pintype "passive"))
      (node (ref "R39") (pin "1") (pinfunction "1_1") (pintype "passive"))
      (node (ref "X1") (pin "23") (pinfunction "23_23") (pintype "passive"))
    )
    (net (code "19") (name "/CH_17") (class "Default")
      (node (ref "R20") (pin "2") (pinfunction "2_2") (pintype "passive"))
      (node (ref "R40") (pin "1") (pinfunction "1_1") (pintype "passive"))
      (node (ref "X1") (pin "7") (pinfunction "7_7") (pintype "passive"))
    )
    (net (code "20") (name "/CH_18") (class "Default")
      (node (ref "R21") (pin "2") (pinfunction "2_2") (pintype "passive"))
      (node (ref "R41") (pin "1") (pinfunction "1_1") (pintype "passive"))
      (node (ref "X1") (pin "22") (pinfunction "22_22") (pintype "passive"))
    )
    (net (code "21") (name "/CH_19") (class "Default")
      (node (ref "R22") (pin "2") (pinfunction "2_2") (pintype "passive"))
      (node (ref "R42") (pin "1") (pinfunction "1_1") (pintype "passive"))
      (node (ref "X1") (pin "6") (pinfunction "6_6") (pintype "passive"))
    )
    (net (code "22") (name "/CH_20") (class "Default")
      (node (ref "R23") (pin "2") (pinfunction "2_2") (pintype "passive"))
      (node (ref "R43") (pin "1") (pinfunction "1_1") (pintype "passive"))
      (node (ref "X1") (pin "21") (pinfunction "21_21") (pintype "passive"))
    )
    (net (code "23") (name "/CH_noF_1") (class "Default")
      (node (ref "C14") (pin "1") (pinfunction "1_1") (pintype "passive"))
      (node (ref "R4") (pin "1") (pinfunction "1_1") (pintype "passive"))
      (node (ref "R44") (pin "2") (pinfunction "2_2") (pintype "passive"))
      (node (ref "U4") (pin "16") (pinfunction "CH1_16") (pintype "passive"))
    )
    (net (code "24") (name "/CH_noF_2") (class "Default")
      (node (ref "C16") (pin "1") (pinfunction "1_1") (pintype "passive"))
      (node (ref "R44") (pin "1") (pinfunction "1_1") (pintype "passive"))
      (node (ref "R45") (pin "2") (pinfunction "2_2") (pintype "passive"))
      (node (ref "R5") (pin "1") (pinfunction "1_1") (pintype "passive"))
      (node (ref "U4") (pin "17") (pinfunction "CH2_17") (pintype "passive"))
    )
    (net (code "25") (name "/CH_noF_3") (class "Default")
      (node (ref "C18") (pin "1") (pinfunction "1_1") (pintype "passive"))
      (node (ref "R45") (pin "1") (pinfunction "1_1") (pintype "passive"))
      (node (ref "R46") (pin "2") (pinfunction "2_2") (pintype "passive"))
      (node (ref "R6") (pin "1") (pinfunction "1_1") (pintype "passive"))
      (node (ref "U4") (pin "18") (pinfunction "CH3_18") (pintype "passive"))
    )
    (net (code "26") (name "/CH_noF_4") (class "Default")
      (node (ref "C20") (pin "1") (pinfunction "1_1") (pintype "passive"))
      (node (ref "R46") (pin "1") (pinfunction "1_1") (pintype "passive"))
      (node (ref "R47") (pin "2") (pinfunction "2_2") (pintype "passive"))
      (node (ref "R7") (pin "1") (pinfunction "1_1") (pintype "passive"))
      (node (ref "U4") (pin "19") (pinfunction "CH4_19") (pintype "passive"))
    )
    (net (code "27") (name "/COM") (class "Default")
      (node (ref "R3") (pin "1") (pinfunction "1_1") (pintype "passive"))
      (node (ref "R47") (pin "1") (pinfunction "1_1") (pintype "passive"))
      (node (ref "U4") (pin "36") (pinfunction "COM_36") (pintype "passive"))
      (node (ref "X1") (pin "1") (pinfunction "1_1") (pintype "passive"))
      (node (ref "X1") (pin "16") (pinfunction "16_16") (pintype "passive"))
      (node (ref "X1") (pin "17") (pinfunction "17_17") (pintype "passive"))
      (node (ref "X1") (pin "18") (pinfunction "18_18") (pintype "passive"))
      (node (ref "X1") (pin "19") (pinfunction "19_19") (pintype "passive"))
      (node (ref "X1") (pin "2") (pinfunction "2_2") (pintype "passive"))
      (node (ref "X1") (pin "20") (pinfunction "20_20") (pintype "passive"))
      (node (ref "X1") (pin "3") (pinfunction "3_3") (pintype "passive"))
      (node (ref "X1") (pin "4") (pinfunction "4_4") (pintype "passive"))
      (node (ref "X1") (pin "5") (pinfunction "5_5") (pintype "passive"))
    )
    (net (code "28") (name "/DCLK") (class "Default")
      (node (ref "U2") (pin "9") (pinfunction "DCLK_9") (pintype "passive"))
    )
    (net (code "29") (name "/GND_ISOLIERT") (class "Default")
      (node (ref "C10") (pin "2") (pinfunction "2_2") (pintype "passive"))
      (node (ref "C11") (pin "1") (pinfunction "1_1") (pintype "passive"))
      (node (ref "C12") (pin "1") (pinfunction "1_1") (pintype "passive"))
      (node (ref "C13") (pin "1") (pinfunction "1_1") (pintype "passive"))
      (node (ref "C14") (pin "2") (pinfunction "2_2") (pintype "passive"))
      (node (ref "C15") (pin "1") (pinfunction "1_1") (pintype "passive"))
      (node (ref "C16") (pin "2") (pinfunction "2_2") (pintype "passive"))
      (node (ref "C17") (pin "1") (pinfunction "1_1") (pintype "passive"))
      (node (ref "C18") (pin "2") (pinfunction "2_2") (pintype "passive"))
      (node (ref "C19") (pin "1") (pinfunction "1_1") (pintype "passive"))
      (node (ref "C2") (pin "2") (pinfunction "2_2") (pintype "passive"))
      (node (ref "C20") (pin "2") (pinfunction "2_2") (pintype "passive"))
      (node (ref "C21") (pin "1") (pinfunction "1_1") (pintype "passive"))
      (node (ref "C22") (pin "2") (pinfunction "2_2") (pintype "passive"))
      (node (ref "C23") (pin "1") (pinfunction "1_1") (pintype "passive"))
      (node (ref "C24") (pin "2") (pinfunction "2_2") (pintype "passive"))
      (node (ref "C25") (pin "1") (pinfunction "1_1") (pintype "passive"))
      (node (ref "C26") (pin "2") (pinfunction "2_2") (pintype "passive"))
      (node (ref "C27") (pin "1") (pinfunction "1_1") (pintype "passive"))
      (node (ref "C28") (pin "2") (pinfunction "2_2") (pintype "passive"))
      (node (ref "C29") (pin "1") (pinfunction "1_1") (pintype "passive"))
      (node (ref "C30") (pin "2") (pinfunction "2_2") (pintype "passive"))
      (node (ref "C31") (pin "1") (pinfunction "1_1") (pintype "passive"))
      (node (ref "C32") (pin "2") (pinfunction "2_2") (pintype "passive"))
      (node (ref "C33") (pin "1") (pinfunction "1_1") (pintype "passive"))
      (node (ref "C4") (pin "1") (pinfunction "1_1") (pintype "passive"))
      (node (ref "C5") (pin "2") (pinfunction "2_2") (pintype "passive"))
      (node (ref "C7") (pin "2") (pinfunction "2_2") (pintype "passive"))
      (node (ref "C8") (pin "1") (pinfunction "1_1") (pintype "passive"))
      (node (ref "D1") (pin "1") (pinfunction "K_1") (pintype "passive"))
      (node (ref "R3") (pin "2") (pinfunction "2_2") (pintype "passive"))
      (node (ref "U2") (pin "11") (pinfunction "GND2_11") (pintype "passive"))
      (node (ref "U2") (pin "19") (pinfunction "GND2_19") (pintype "passive"))
      (node (ref "U3") (pin "4") (pinfunction "GND_4") (pintype "passive"))
      (node (ref "U4") (pin "1") (pinfunction "GND_1") (pintype "passive"))
      (node (ref "U4") (pin "12") (pinfunction "GND_12") (pintype "passive"))
      (node (ref "U4") (pin "15") (pinfunction "GND_15") (pintype "passive"))
      (node (ref "U4") (pin "3") (pinfunction "GND_3") (pintype "passive"))
      (node (ref "U4") (pin "44") (pinfunction "GND_44") (pintype "passive"))
      (node (ref "U4") (pin "5") (pinfunction "GND_5") (pintype "passive"))
      (node (ref "U4") (pin "7") (pinfunction "GND_7") (pintype "passive"))
      (node (ref "U4") (pin "9") (pinfunction "GND_9") (pintype "passive"))
    )
    (net (code "30") (name "/MCLK") (class "Default")
      (node (ref "U2") (pin "3") (pinfunction "MCLK_3") (pintype "passive"))
    )
    (net (code "31") (name "/MI") (class "Default")
      (node (ref "U2") (pin "5") (pinfunction "MI_5") (pintype "passive"))
    )
    (net (code "32") (name "/MO") (class "Default")
      (node (ref "U2") (pin "4") (pinfunction "MO_4") (pintype "passive"))
    )
    (net (code "33") (name "/VIA") (class "Default")
      (node (ref "U2") (pin "7") (pinfunction "VIA_7") (pintype "passive"))
    )
    (net (code "34") (name "/VOB") (class "Default")
      (node (ref "U2") (pin "8") (pinfunction "VOB_8") (pintype "passive"))
    )
    (net (code "35") (name "/{slash}MSS") (class "Default")
      (node (ref "U2") (pin "6") (pinfunction "~{MSS}_6") (pintype "passive"))
    )
    (net (code "36") (name "GND") (class "Default")
      (node (ref "C1") (pin "1") (pinfunction "1_1") (pintype "passive"))
      (node (ref "C3") (pin "1") (pinfunction "1_1") (pintype "passive"))
      (node (ref "C6") (pin "1") (pinfunction "1_1") (pintype "passive"))
      (node (ref "U2") (pin "10") (pinfunction "GND1_10") (pintype "passive"))
      (node (ref "U2") (pin "2") (pinfunction "GND1_2") (pintype "passive"))
      (node (ref "U3") (pin "2") (pinfunction "Vin-_2") (pintype "passive"))
    )
    (net (code "37") (name "Net-(D1-A)") (class "Default")
      (node (ref "D1") (pin "2") (pinfunction "A_2") (pintype "passive"))
      (node (ref "R2") (pin "2") (pinfunction "2_2") (pintype "passive"))
    )
    (net (code "38") (name "Net-(R24-Pad2)") (class "Default")
      (node (ref "R24") (pin "2") (pinfunction "2_2") (pintype "passive"))
      (node (ref "R25") (pin "2") (pinfunction "2_2") (pintype "passive"))
      (node (ref "R26") (pin "2") (pinfunction "2_2") (pintype "passive"))
      (node (ref "R27") (pin "2") (pinfunction "2_2") (pintype "passive"))
      (node (ref "R28") (pin "2") (pinfunction "2_2") (pintype "passive"))
      (node (ref "R29") (pin "2") (pinfunction "2_2") (pintype "passive"))
      (node (ref "R30") (pin "2") (pinfunction "2_2") (pintype "passive"))
      (node (ref "R31") (pin "2") (pinfunction "2_2") (pintype "passive"))
      (node (ref "R32") (pin "2") (pinfunction "2_2") (pintype "passive"))
      (node (ref "R33") (pin "2") (pinfunction "2_2") (pintype "passive"))
      (node (ref "R34") (pin "2") (pinfunction "2_2") (pintype "passive"))
      (node (ref "R35") (pin "2") (pinfunction "2_2") (pintype "passive"))
      (node (ref "R36") (pin "2") (pinfunction "2_2") (pintype "passive"))
      (node (ref "R37") (pin "2") (pinfunction "2_2") (pintype "passive"))
      (node (ref "R38") (pin "2") (pinfunction "2_2") (pintype "passive"))
      (node (ref "R39") (pin "2") (pinfunction "2_2") (pintype "passive"))
      (node (ref "R40") (pin "2") (pinfunction "2_2") (pintype "passive"))
      (node (ref "R41") (pin "2") (pinfunction "2_2") (pintype "passive"))
      (node (ref "R42") (pin "2") (pinfunction "2_2") (pintype "passive"))
      (node (ref "R43") (pin "2") (pinfunction "2_2") (pintype "passive"))
    )
    (net (code "39") (name "Net-(U2-SCLK)") (class "Default")
      (node (ref "U2") (pin "18") (pinfunction "SCLK_18") (pintype "passive"))
      (node (ref "U4") (pin "38") (pinfunction "SCK_38") (pintype "passive"))
    )
    (net (code "40") (name "Net-(U2-SI)") (class "Default")
      (node (ref "U2") (pin "17") (pinfunction "SI_17") (pintype "passive"))
      (node (ref "U4") (pin "40") (pinfunction "SDI_40") (pintype "passive"))
    )
    (net (code "41") (name "Net-(U2-SO)") (class "Default")
      (node (ref "U2") (pin "16") (pinfunction "SO_16") (pintype "passive"))
      (node (ref "U4") (pin "39") (pinfunction "SDO_39") (pintype "passive"))
    )
    (net (code "42") (name "Net-(U2-VIB)") (class "Default")
      (node (ref "U2") (pin "13") (pinfunction "VIB_13") (pintype "passive"))
      (node (ref "U4") (pin "37") (pinfunction "INTERRUPT_37") (pintype "passive"))
    )
    (net (code "43") (name "Net-(U2-VOA)") (class "Default")
      (node (ref "R1") (pin "1") (pinfunction "1_1") (pintype "passive"))
      (node (ref "U2") (pin "14") (pinfunction "VOA_14") (pintype "passive"))
      (node (ref "U4") (pin "42") (pinfunction "~{RESET}_42") (pintype "passive"))
    )
    (net (code "44") (name "Net-(U2-~{SSS})") (class "Default")
      (node (ref "U2") (pin "15") (pinfunction "~{SSS}_15") (pintype "passive"))
      (node (ref "U4") (pin "41") (pinfunction "~{CS}_41") (pintype "passive"))
    )
    (net (code "45") (name "Net-(U4-CH5)") (class "Default")
      (node (ref "C22") (pin "1") (pinfunction "1_1") (pintype "passive"))
      (node (ref "R8") (pin "1") (pinfunction "1_1") (pintype "passive"))
      (node (ref "U4") (pin "20") (pinfunction "CH5_20") (pintype "passive"))
    )
    (net (code "46") (name "Net-(U4-CH6)") (class "Default")
      (node (ref "C24") (pin "1") (pinfunction "1_1") (pintype "passive"))
      (node (ref "R9") (pin "1") (pinfunction "1_1") (pintype "passive"))
      (node (ref "U4") (pin "21") (pinfunction "CH6_21") (pintype "passive"))
    )
    (net (code "47") (name "Net-(U4-CH7)") (class "Default")
      (node (ref "C26") (pin "1") (pinfunction "1_1") (pintype "passive"))
      (node (ref "R10") (pin "1") (pinfunction "1_1") (pintype "passive"))
      (node (ref "U4") (pin "22") (pinfunction "CH7_22") (pintype "passive"))
    )
    (net (code "48") (name "Net-(U4-CH8)") (class "Default")
      (node (ref "C28") (pin "1") (pinfunction "1_1") (pintype "passive"))
      (node (ref "R11") (pin "1") (pinfunction "1_1") (pintype "passive"))
      (node (ref "U4") (pin "23") (pinfunction "CH8_23") (pintype "passive"))
    )
    (net (code "49") (name "Net-(U4-CH9)") (class "Default")
      (node (ref "C30") (pin "1") (pinfunction "1_1") (pintype "passive"))
      (node (ref "R12") (pin "1") (pinfunction "1_1") (pintype "passive"))
      (node (ref "U4") (pin "24") (pinfunction "CH9_24") (pintype "passive"))
    )
    (net (code "50") (name "Net-(U4-CH10)") (class "Default")
      (node (ref "C32") (pin "1") (pinfunction "1_1") (pintype "passive"))
      (node (ref "R13") (pin "1") (pinfunction "1_1") (pintype "passive"))
      (node (ref "U4") (pin "25") (pinfunction "CH10_25") (pintype "passive"))
    )
    (net (code "51") (name "Net-(U4-CH11)") (class "Default")
      (node (ref "C33") (pin "2") (pinfunction "2_2") (pintype "passive"))
      (node (ref "R14") (pin "1") (pinfunction "1_1") (pintype "passive"))
      (node (ref "U4") (pin "26") (pinfunction "CH11_26") (pintype "passive"))
    )
    (net (code "52") (name "Net-(U4-CH12)") (class "Default")
      (node (ref "C31") (pin "2") (pinfunction "2_2") (pintype "passive"))
      (node (ref "R15") (pin "1") (pinfunction "1_1") (pintype "passive"))
      (node (ref "U4") (pin "27") (pinfunction "CH12_27") (pintype "passive"))
    )
    (net (code "53") (name "Net-(U4-CH13)") (class "Default")
      (node (ref "C29") (pin "2") (pinfunction "2_2") (pintype "passive"))
      (node (ref "R16") (pin "1") (pinfunction "1_1") (pintype "passive"))
      (node (ref "U4") (pin "28") (pinfunction "CH13_28") (pintype "passive"))
    )
    (net (code "54") (name "Net-(U4-CH14)") (class "Default")
      (node (ref "C27") (pin "2") (pinfunction "2_2") (pintype "passive"))
      (node (ref "R17") (pin "1") (pinfunction "1_1") (pintype "passive"))
      (node (ref "U4") (pin "29") (pinfunction "CH14_29") (pintype "passive"))
    )
    (net (code "55") (name "Net-(U4-CH15)") (class "Default")
      (node (ref "C25") (pin "2") (pinfunction "2_2") (pintype "passive"))
      (node (ref "R18") (pin "1") (pinfunction "1_1") (pintype "passive"))
      (node (ref "U4") (pin "30") (pinfunction "CH15_30") (pintype "passive"))
    )
    (net (code "56") (name "Net-(U4-CH16)") (class "Default")
      (node (ref "C23") (pin "2") (pinfunction "2_2") (pintype "passive"))
      (node (ref "R19") (pin "1") (pinfunction "1_1") (pintype "passive"))
      (node (ref "U4") (pin "31") (pinfunction "CH16_31") (pintype "passive"))
    )
    (net (code "57") (name "Net-(U4-CH17)") (class "Default")
      (node (ref "C21") (pin "2") (pinfunction "2_2") (pintype "passive"))
      (node (ref "R20") (pin "1") (pinfunction "1_1") (pintype "passive"))
      (node (ref "U4") (pin "32") (pinfunction "CH17_32") (pintype "passive"))
    )
    (net (code "58") (name "Net-(U4-CH18)") (class "Default")
      (node (ref "C19") (pin "2") (pinfunction "2_2") (pintype "passive"))
      (node (ref "R21") (pin "1") (pinfunction "1_1") (pintype "passive"))
      (node (ref "U4") (pin "33") (pinfunction "CH18_33") (pintype "passive"))
    )
    (net (code "59") (name "Net-(U4-CH19)") (class "Default")
      (node (ref "C17") (pin "2") (pinfunction "2_2") (pintype "passive"))
      (node (ref "R22") (pin "1") (pinfunction "1_1") (pintype "passive"))
      (node (ref "U4") (pin "34") (pinfunction "CH19_34") (pintype "passive"))
    )
    (net (code "60") (name "Net-(U4-CH20)") (class "Default")
      (node (ref "C15") (pin "2") (pinfunction "2_2") (pintype "passive"))
      (node (ref "R23") (pin "1") (pinfunction "1_1") (pintype "passive"))
      (node (ref "U4") (pin "35") (pinfunction "CH20_35") (pintype "passive"))
    )
    (net (code "61") (name "Net-(U4-LDO)") (class "Default")
      (node (ref "C8") (pin "2") (pinfunction "2_2") (pintype "passive"))
      (node (ref "U4") (pin "43") (pinfunction "LDO_43") (pintype "passive"))
    )
    (net (code "62") (name "Net-(U4-Q1)") (class "Default")
      (node (ref "C9") (pin "1") (pinfunction "1_1") (pintype "passive"))
      (node (ref "U4") (pin "48") (pinfunction "Q1_48") (pintype "passive"))
    )
    (net (code "63") (name "Net-(U4-Q2)") (class "Default")
      (node (ref "C9") (pin "2") (pinfunction "2_2") (pintype "passive"))
      (node (ref "U4") (pin "47") (pinfunction "Q2_47") (pintype "passive"))
    )
    (net (code "64") (name "Net-(U4-Q3)") (class "Default")
      (node (ref "C4") (pin "2") (pinfunction "2_2") (pintype "passive"))
      (node (ref "U4") (pin "46") (pinfunction "Q3_46") (pintype "passive"))
    )
    (net (code "65") (name "Net-(U4-VREF_BYP)") (class "Default")
      (node (ref "C2") (pin "1") (pinfunction "1_1") (pintype "passive"))
      (node (ref "C5") (pin "1") (pinfunction "1_1") (pintype "passive"))
      (node (ref "U4") (pin "11") (pinfunction "VREF_BYP_11") (pintype "passive"))
    )
    (net (code "66") (name "Net-(U4-VREF_OUT)") (class "Default")
      (node (ref "C10") (pin "1") (pinfunction "1_1") (pintype "passive"))
      (node (ref "C7") (pin "1") (pinfunction "1_1") (pintype "passive"))
      (node (ref "U4") (pin "13") (pinfunction "VREF_OUT_13") (pintype "passive"))
      (node (ref "U4") (pin "14") (pinfunction "VREF_P_14") (pintype "passive"))
    )
    (net (code "67") (name "VCC_Fused") (class "Default")
      (node (ref "C3") (pin "2") (pinfunction "2_2") (pintype "passive"))
      (node (ref "C6") (pin "2") (pinfunction "2_2") (pintype "passive"))
      (node (ref "U3") (pin "1") (pinfunction "Vin+_1") (pintype "passive"))
    )
  )
)
